# Power-MCU-Breakout.net
KiCad netlist of a schematic drawn in Altium Designer
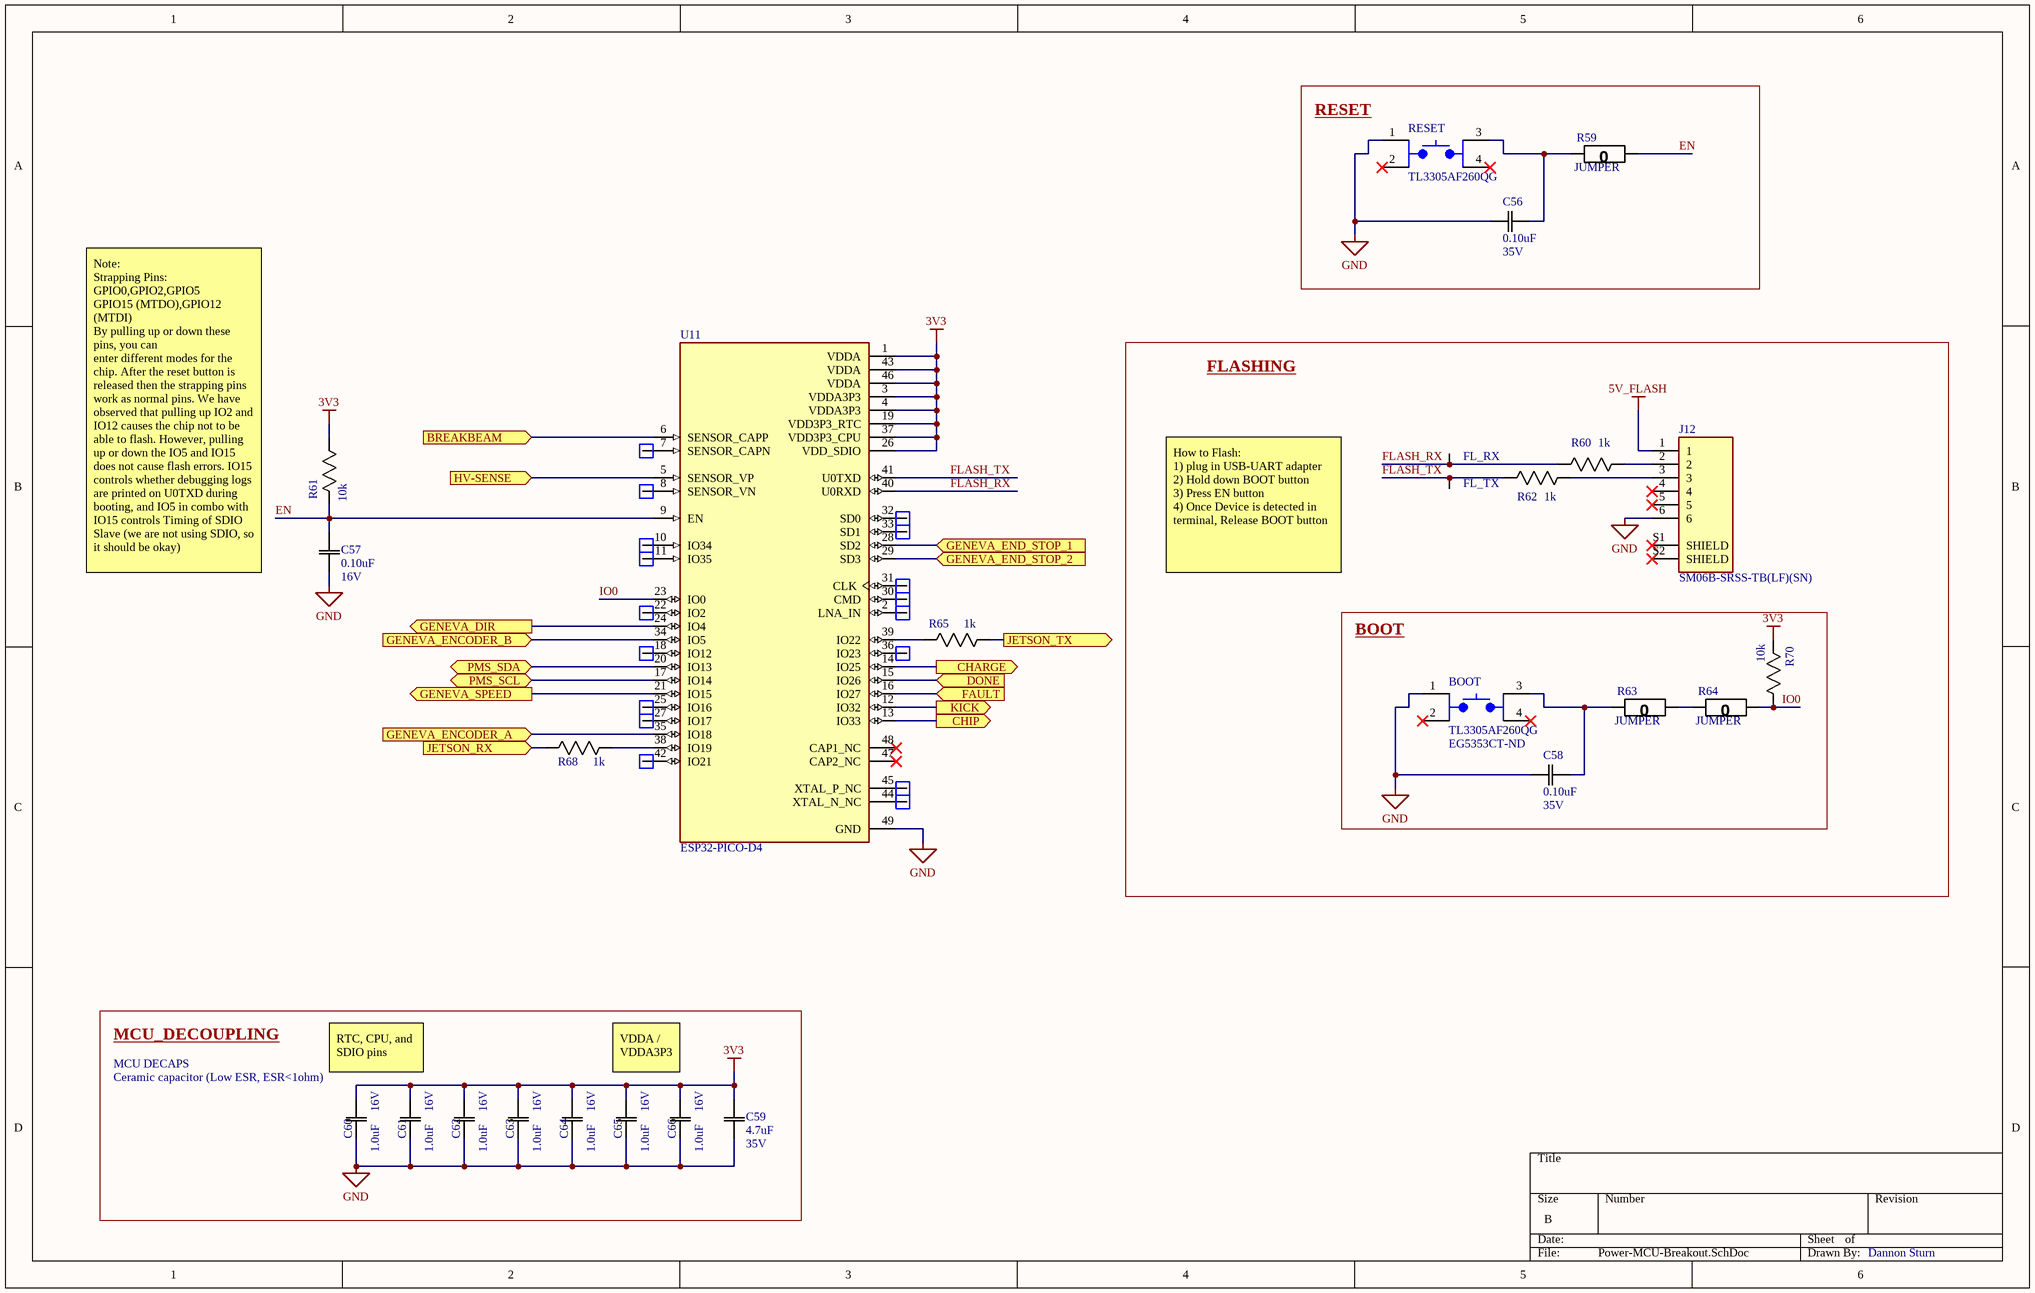
[diagram p0: Power-MCU-Breakout.SchDoc]

(export (version "E")
  (design (tool "Eeschema 10.0.6"))
  (components
    (comp (ref "2")
      (value "Breakout Pin 0603")
      (footprint "BreakoutPin 0603")
      (libsource (lib "AltiumLibraries") (part "Breakout Pin 0603"))
    )
    (comp (ref "7")
      (value "Breakout Pin 0603")
      (footprint "BreakoutPin 0603")
      (libsource (lib "AltiumLibraries") (part "Breakout Pin 0603"))
    )
    (comp (ref "8")
      (value "Breakout Pin 0603")
      (footprint "BreakoutPin 0603")
      (libsource (lib "AltiumLibraries") (part "Breakout Pin 0603"))
    )
    (comp (ref "10")
      (value "Breakout Pin 0603")
      (footprint "BreakoutPin 0603")
      (libsource (lib "AltiumLibraries") (part "Breakout Pin 0603"))
    )
    (comp (ref "11")
      (value "Breakout Pin 0603")
      (footprint "BreakoutPin 0603")
      (libsource (lib "AltiumLibraries") (part "Breakout Pin 0603"))
    )
    (comp (ref "18")
      (value "Breakout Pin 0603")
      (footprint "BreakoutPin 0603")
      (libsource (lib "AltiumLibraries") (part "Breakout Pin 0603"))
    )
    (comp (ref "22")
      (value "Breakout Pin 0603")
      (footprint "BreakoutPin 0603")
      (libsource (lib "AltiumLibraries") (part "Breakout Pin 0603"))
    )
    (comp (ref "25")
      (value "Breakout Pin 0603")
      (footprint "BreakoutPin 0603")
      (libsource (lib "AltiumLibraries") (part "Breakout Pin 0603"))
    )
    (comp (ref "27")
      (value "Breakout Pin 0603")
      (footprint "BreakoutPin 0603")
      (libsource (lib "AltiumLibraries") (part "Breakout Pin 0603"))
    )
    (comp (ref "30")
      (value "Breakout Pin 0603")
      (footprint "BreakoutPin 0603")
      (libsource (lib "AltiumLibraries") (part "Breakout Pin 0603"))
    )
    (comp (ref "31")
      (value "Breakout Pin 0603")
      (footprint "BreakoutPin 0603")
      (libsource (lib "AltiumLibraries") (part "Breakout Pin 0603"))
    )
    (comp (ref "32")
      (value "Breakout Pin 0603")
      (footprint "BreakoutPin 0603")
      (libsource (lib "AltiumLibraries") (part "Breakout Pin 0603"))
    )
    (comp (ref "33")
      (value "Breakout Pin 0603")
      (footprint "BreakoutPin 0603")
      (libsource (lib "AltiumLibraries") (part "Breakout Pin 0603"))
    )
    (comp (ref "36")
      (value "Breakout Pin 0603")
      (footprint "BreakoutPin 0603")
      (libsource (lib "AltiumLibraries") (part "Breakout Pin 0603"))
    )
    (comp (ref "42")
      (value "Breakout Pin 0603")
      (footprint "BreakoutPin 0603")
      (libsource (lib "AltiumLibraries") (part "Breakout Pin 0603"))
    )
    (comp (ref "44")
      (value "Breakout Pin 0603")
      (footprint "BreakoutPin 0603")
      (libsource (lib "AltiumLibraries") (part "Breakout Pin 0603"))
    )
    (comp (ref "45")
      (value "Breakout Pin 0603")
      (footprint "BreakoutPin 0603")
      (libsource (lib "AltiumLibraries") (part "Breakout Pin 0603"))
    )
    (comp (ref "BOOT")
      (value "TL3305AF260QG")
      (footprint "SW_TL3305AF260QG")
      (description "Tactile Switch SPST-NO Top Actuated Surface Mount")
      (fields (field (name "MF") "E-Switch") (field (name "SUPPLIER PART NUMBER 1") "EG5353CT-ND"))
      (libsource (lib "AltiumLibraries") (part "SW PUSH TACT NO SMD"))
    )
    (comp (ref "C56")
      (value "0.10uF")
      (footprint "0603")
      (description "CAP CER 0.10UF 35V X7R 0603/0805")
      (fields (field (name "TOLERANCE") "10%") (field (name "RATING") "35V"))
      (libsource (lib "AltiumLibraries") (part "CAP 0.10uF 35V"))
    )
    (comp (ref "C57")
      (value "0.10uF")
      (footprint "0603")
      (description "CAP CER 0.10UF 16V X5R 0603/0805")
      (fields (field (name "TOLERANCE") "10%") (field (name "RATING") "16V"))
      (libsource (lib "AltiumLibraries") (part "CAP 0.10uF 16V"))
    )
    (comp (ref "C58")
      (value "0.10uF")
      (footprint "0603")
      (description "CAP CER 0.10UF 35V X7R 0603/0805")
      (fields (field (name "TOLERANCE") "10%") (field (name "RATING") "35V"))
      (libsource (lib "AltiumLibraries") (part "CAP 0.10uF 35V"))
    )
    (comp (ref "C59")
      (value "4.7uF")
      (footprint "0603")
      (description "CAP CER 4.7UF 35V X7R 0603/0805")
      (fields (field (name "TOLERANCE") "10%") (field (name "RATING") "35V"))
      (libsource (lib "AltiumLibraries") (part "CAP 4.7uF 35V"))
    )
    (comp (ref "C60")
      (value "1.0uF")
      (footprint "0603")
      (description "CAP CER 1.0UF 16V X5R 0603/0805")
      (fields (field (name "TOLERANCE") "10%") (field (name "RATING") "16V"))
      (libsource (lib "AltiumLibraries") (part "CAP 1.0uF 16V"))
    )
    (comp (ref "C61")
      (value "1.0uF")
      (footprint "0603")
      (description "CAP CER 1.0UF 16V X5R 0603/0805")
      (fields (field (name "TOLERANCE") "10%") (field (name "RATING") "16V"))
      (libsource (lib "AltiumLibraries") (part "CAP 1.0uF 16V"))
    )
    (comp (ref "C62")
      (value "1.0uF")
      (footprint "0603")
      (description "CAP CER 1.0UF 16V X5R 0603/0805")
      (fields (field (name "TOLERANCE") "10%") (field (name "RATING") "16V"))
      (libsource (lib "AltiumLibraries") (part "CAP 1.0uF 16V"))
    )
    (comp (ref "C63")
      (value "1.0uF")
      (footprint "0603")
      (description "CAP CER 1.0UF 16V X5R 0603/0805")
      (fields (field (name "TOLERANCE") "10%") (field (name "RATING") "16V"))
      (libsource (lib "AltiumLibraries") (part "CAP 1.0uF 16V"))
    )
    (comp (ref "C64")
      (value "1.0uF")
      (footprint "0603")
      (description "CAP CER 1.0UF 16V X5R 0603/0805")
      (fields (field (name "TOLERANCE") "10%") (field (name "RATING") "16V"))
      (libsource (lib "AltiumLibraries") (part "CAP 1.0uF 16V"))
    )
    (comp (ref "C65")
      (value "1.0uF")
      (footprint "0603")
      (description "CAP CER 1.0UF 16V X5R 0603/0805")
      (fields (field (name "TOLERANCE") "10%") (field (name "RATING") "16V"))
      (libsource (lib "AltiumLibraries") (part "CAP 1.0uF 16V"))
    )
    (comp (ref "C66")
      (value "1.0uF")
      (footprint "0603")
      (description "CAP CER 1.0UF 16V X5R 0603/0805")
      (fields (field (name "TOLERANCE") "10%") (field (name "RATING") "16V"))
      (libsource (lib "AltiumLibraries") (part "CAP 1.0uF 16V"))
    )
    (comp (ref "FL_RX")
      (value "Test Point (Via)")
      (footprint "TP")
      (libsource (lib "AltiumLibraries") (part "Test Point (Via)"))
    )
    (comp (ref "FL_TX")
      (value "Test Point (Via)")
      (footprint "TP")
      (libsource (lib "AltiumLibraries") (part "Test Point (Via)"))
    )
    (comp (ref "J12")
      (value "SM06B-SRSS-TB(LF)(SN)")
      (footprint "JST_SM06B-SRSS-TB(LF)(SN)")
      (description "Connector Header Surface Mount, Right Angle 6 position 0.039 _1.00mm_")
      (fields
        (field (name "MP") "SM06B-SRSS-TB_LF__SN_")
        (field (name "DIGI-KEY_PART_NUMBER") "455-1806-1-ND")
      )
      (libsource (lib "AltiumLibraries") (part "CN 6POS JST SR SMT"))
    )
    (comp (ref "R59")
      (value "JUMPER")
      (footprint "0603")
      (description "RES SMD 0 OHM JUMPER GENERIC 0805/0603")
      (libsource (lib "AltiumLibraries") (part "RES 0 JUMPER"))
    )
    (comp (ref "R60")
      (value "1k")
      (footprint "0603")
      (description "RES SMD 1K OHM 1% 1/8W 0603/0805")
      (fields (field (name "TOLERANCE") "1%"))
      (libsource (lib "AltiumLibraries") (part "RES 1k 1/8W - 1%"))
    )
    (comp (ref "R61")
      (value "10k")
      (footprint "0603")
      (description "RES SMD 10K OHM 5% 1/8W 0805/0603")
      (fields (field (name "TOLERANCE") "5%"))
      (libsource (lib "") (part "RES 10k 1/8W - 5%_1"))
    )
    (comp (ref "R62")
      (value "1k")
      (footprint "0603")
      (description "RES SMD 1K OHM 1% 1/8W 0603/0805")
      (fields (field (name "TOLERANCE") "1%"))
      (libsource (lib "AltiumLibraries") (part "RES 1k 1/8W - 1%"))
    )
    (comp (ref "R63")
      (value "JUMPER")
      (footprint "0603")
      (description "RES SMD 0 OHM JUMPER GENERIC 0805/0603")
      (libsource (lib "AltiumLibraries") (part "RES 0 JUMPER"))
    )
    (comp (ref "R64")
      (value "JUMPER")
      (footprint "0603")
      (description "RES SMD 0 OHM JUMPER GENERIC 0805/0603")
      (libsource (lib "AltiumLibraries") (part "RES 0 JUMPER"))
    )
    (comp (ref "R65")
      (value "1k")
      (footprint "0603")
      (description "RES SMD 1K OHM 1% 1/8W 0603/0805")
      (fields (field (name "TOLERANCE") "1%"))
      (libsource (lib "AltiumLibraries") (part "RES 1k 1/8W - 1%"))
    )
    (comp (ref "R68")
      (value "1k")
      (footprint "0603")
      (description "RES SMD 1K OHM 1% 1/8W 0603/0805")
      (fields (field (name "TOLERANCE") "1%"))
      (libsource (lib "AltiumLibraries") (part "RES 1k 1/8W - 1%"))
    )
    (comp (ref "R70")
      (value "10k")
      (footprint "0603")
      (description "RES SMD 10K OHM 5% 1/8W 0805/0603")
      (fields (field (name "TOLERANCE") "5%"))
      (libsource (lib "AltiumLibraries") (part "RES 10k 1/8W - 5%"))
    )
    (comp (ref "RESET")
      (value "TL3305AF260QG")
      (footprint "SW_TL3305AF260QG")
      (description "Tactile Switch SPST-NO Top Actuated Surface Mount")
      (fields (field (name "MF") "E-Switch"))
      (libsource (lib "AltiumLibraries") (part "SW PUSH TACT NO SMD"))
    )
    (comp (ref "U11")
      (value "ESP32-PICO-D4")
      (footprint "PQFN50P700X700X104-49N - BigPads")
      (fields (field (name "MF") "Espressif Systems"))
      (libsource (lib "AltiumLibraries") (part "ESP32-PICO-D4"))
    )
  )
  (nets
    (net (code "1") (name "/BREAKBEAM") (class "Default")
      (node (ref "U11") (pin "6") (pinfunction "SENSOR_CAPP_6") (pintype "input"))
    )
    (net (code "2") (name "/CHARGE") (class "Default")
      (node (ref "U11") (pin "14") (pinfunction "IO25_14") (pintype "bidirectional"))
    )
    (net (code "3") (name "/CHIP") (class "Default")
      (node (ref "U11") (pin "13") (pinfunction "IO33_13") (pintype "bidirectional"))
    )
    (net (code "4") (name "/DONE") (class "Default")
      (node (ref "U11") (pin "15") (pinfunction "IO26_15") (pintype "bidirectional"))
    )
    (net (code "5") (name "/EN") (class "Default")
      (node (ref "C57") (pin "2") (pinfunction "C2_2") (pintype "passive"))
      (node (ref "R59") (pin "1") (pinfunction "R1_1") (pintype "passive"))
      (node (ref "R61") (pin "2") (pinfunction "R2_2") (pintype "passive"))
      (node (ref "U11") (pin "9") (pinfunction "EN_9") (pintype "input"))
    )
    (net (code "6") (name "/FAULT") (class "Default")
      (node (ref "U11") (pin "16") (pinfunction "IO27_16") (pintype "bidirectional"))
    )
    (net (code "7") (name "/FLASH_RX") (class "Default")
      (node (ref "FL_RX") (pin "1") (pinfunction "1_1") (pintype "passive"))
      (node (ref "R60") (pin "2") (pinfunction "R2_2") (pintype "passive"))
      (node (ref "U11") (pin "40") (pinfunction "U0RXD_40") (pintype "bidirectional"))
    )
    (net (code "8") (name "/FLASH_TX") (class "Default")
      (node (ref "FL_TX") (pin "1") (pinfunction "1_1") (pintype "passive"))
      (node (ref "R62") (pin "2") (pinfunction "R2_2") (pintype "passive"))
      (node (ref "U11") (pin "41") (pinfunction "U0TXD_41") (pintype "bidirectional"))
    )
    (net (code "9") (name "/GENEVA_DIR") (class "Default")
      (node (ref "U11") (pin "24") (pinfunction "IO4_24") (pintype "bidirectional"))
    )
    (net (code "10") (name "/GENEVA_ENCODER_A") (class "Default")
      (node (ref "U11") (pin "35") (pinfunction "IO18_35") (pintype "bidirectional"))
    )
    (net (code "11") (name "/GENEVA_ENCODER_B") (class "Default")
      (node (ref "U11") (pin "34") (pinfunction "IO5_34") (pintype "bidirectional"))
    )
    (net (code "12") (name "/GENEVA_END_STOP_1") (class "Default")
      (node (ref "U11") (pin "28") (pinfunction "SD2_28") (pintype "bidirectional"))
    )
    (net (code "13") (name "/GENEVA_END_STOP_2") (class "Default")
      (node (ref "U11") (pin "29") (pinfunction "SD3_29") (pintype "bidirectional"))
    )
    (net (code "14") (name "/GENEVA_SPEED") (class "Default")
      (node (ref "U11") (pin "21") (pinfunction "IO15_21") (pintype "bidirectional"))
    )
    (net (code "15") (name "/HV-SENSE") (class "Default")
      (node (ref "U11") (pin "5") (pinfunction "SENSOR_VP_5") (pintype "input"))
    )
    (net (code "16") (name "/IO0") (class "Default")
      (node (ref "R64") (pin "1") (pinfunction "R1_1") (pintype "passive"))
      (node (ref "R70") (pin "1") (pinfunction "R1_1") (pintype "passive"))
      (node (ref "U11") (pin "23") (pinfunction "IO0_23") (pintype "bidirectional"))
    )
    (net (code "17") (name "/JETSON_RX") (class "Default")
      (node (ref "R68") (pin "2") (pinfunction "R2_2") (pintype "passive"))
    )
    (net (code "18") (name "/JETSON_TX") (class "Default")
      (node (ref "R65") (pin "1") (pinfunction "R1_1") (pintype "passive"))
    )
    (net (code "19") (name "/KICK") (class "Default")
      (node (ref "U11") (pin "12") (pinfunction "IO32_12") (pintype "bidirectional"))
    )
    (net (code "20") (name "/PMS_SCL") (class "Default")
      (node (ref "U11") (pin "17") (pinfunction "IO14_17") (pintype "bidirectional"))
    )
    (net (code "21") (name "/PMS_SDA") (class "Default")
      (node (ref "U11") (pin "20") (pinfunction "IO13_20") (pintype "bidirectional"))
    )
    (net (code "22") (name "3V3") (class "Default")
      (node (ref "C59") (pin "2") (pinfunction "C2_2") (pintype "passive"))
      (node (ref "C60") (pin "2") (pinfunction "C2_2") (pintype "passive"))
      (node (ref "C61") (pin "2") (pinfunction "C2_2") (pintype "passive"))
      (node (ref "C62") (pin "2") (pinfunction "C2_2") (pintype "passive"))
      (node (ref "C63") (pin "2") (pinfunction "C2_2") (pintype "passive"))
      (node (ref "C64") (pin "2") (pinfunction "C2_2") (pintype "passive"))
      (node (ref "C65") (pin "2") (pinfunction "C2_2") (pintype "passive"))
      (node (ref "C66") (pin "2") (pinfunction "C2_2") (pintype "passive"))
      (node (ref "R61") (pin "1") (pinfunction "R1_1") (pintype "passive"))
      (node (ref "R70") (pin "2") (pinfunction "R2_2") (pintype "passive"))
      (node (ref "U11") (pin "1") (pinfunction "VDDA_1") (pintype "power_in"))
      (node (ref "U11") (pin "19") (pinfunction "VDD3P3_RTC_19") (pintype "power_in"))
      (node (ref "U11") (pin "26") (pinfunction "VDD_SDIO_26") (pintype "power_in"))
      (node (ref "U11") (pin "3") (pinfunction "VDDA3P3_3") (pintype "power_in"))
      (node (ref "U11") (pin "37") (pinfunction "VDD3P3_CPU_37") (pintype "power_in"))
      (node (ref "U11") (pin "4") (pinfunction "VDDA3P3_4") (pintype "power_in"))
      (node (ref "U11") (pin "43") (pinfunction "VDDA_43") (pintype "power_in"))
      (node (ref "U11") (pin "46") (pinfunction "VDDA_46") (pintype "power_in"))
    )
    (net (code "23") (name "5V_FLASH") (class "Default")
      (node (ref "J12") (pin "1") (pinfunction "1_1") (pintype "passive"))
    )
    (net (code "24") (name "GND") (class "Default")
      (node (ref "BOOT") (pin "1") (pinfunction "1_1") (pintype "passive"))
      (node (ref "C56") (pin "1") (pinfunction "C1_1") (pintype "passive"))
      (node (ref "C57") (pin "1") (pinfunction "C1_1") (pintype "passive"))
      (node (ref "C58") (pin "1") (pinfunction "C1_1") (pintype "passive"))
      (node (ref "C59") (pin "1") (pinfunction "C1_1") (pintype "passive"))
      (node (ref "C60") (pin "1") (pinfunction "C1_1") (pintype "passive"))
      (node (ref "C61") (pin "1") (pinfunction "C1_1") (pintype "passive"))
      (node (ref "C62") (pin "1") (pinfunction "C1_1") (pintype "passive"))
      (node (ref "C63") (pin "1") (pinfunction "C1_1") (pintype "passive"))
      (node (ref "C64") (pin "1") (pinfunction "C1_1") (pintype "passive"))
      (node (ref "C65") (pin "1") (pinfunction "C1_1") (pintype "passive"))
      (node (ref "C66") (pin "1") (pinfunction "C1_1") (pintype "passive"))
      (node (ref "J12") (pin "6") (pinfunction "6_6") (pintype "passive"))
      (node (ref "RESET") (pin "1") (pinfunction "1_1") (pintype "passive"))
      (node (ref "U11") (pin "49") (pinfunction "GND_49") (pintype "power_in"))
    )
    (net (code "25") (name "Net-(2-BRKOUT)") (class "Default")
      (node (ref "2") (pin "1") (pinfunction "BRKOUT_1") (pintype "passive"))
      (node (ref "U11") (pin "2") (pinfunction "LNA_IN_2") (pintype "bidirectional"))
    )
    (net (code "26") (name "Net-(7-BRKOUT)") (class "Default")
      (node (ref "7") (pin "1") (pinfunction "BRKOUT_1") (pintype "passive"))
      (node (ref "U11") (pin "7") (pinfunction "SENSOR_CAPN_7") (pintype "input"))
    )
    (net (code "27") (name "Net-(8-BRKOUT)") (class "Default")
      (node (ref "8") (pin "1") (pinfunction "BRKOUT_1") (pintype "passive"))
      (node (ref "U11") (pin "8") (pinfunction "SENSOR_VN_8") (pintype "input"))
    )
    (net (code "28") (name "Net-(10-BRKOUT)") (class "Default")
      (node (ref "10") (pin "1") (pinfunction "BRKOUT_1") (pintype "passive"))
      (node (ref "U11") (pin "10") (pinfunction "IO34_10") (pintype "input"))
    )
    (net (code "29") (name "Net-(11-BRKOUT)") (class "Default")
      (node (ref "11") (pin "1") (pinfunction "BRKOUT_1") (pintype "passive"))
      (node (ref "U11") (pin "11") (pinfunction "IO35_11") (pintype "input"))
    )
    (net (code "30") (name "Net-(18-BRKOUT)") (class "Default")
      (node (ref "18") (pin "1") (pinfunction "BRKOUT_1") (pintype "passive"))
      (node (ref "U11") (pin "18") (pinfunction "IO12_18") (pintype "bidirectional"))
    )
    (net (code "31") (name "Net-(22-BRKOUT)") (class "Default")
      (node (ref "22") (pin "1") (pinfunction "BRKOUT_1") (pintype "passive"))
      (node (ref "U11") (pin "22") (pinfunction "IO2_22") (pintype "bidirectional"))
    )
    (net (code "32") (name "Net-(25-BRKOUT)") (class "Default")
      (node (ref "25") (pin "1") (pinfunction "BRKOUT_1") (pintype "passive"))
      (node (ref "U11") (pin "25") (pinfunction "IO16_25") (pintype "bidirectional"))
    )
    (net (code "33") (name "Net-(27-BRKOUT)") (class "Default")
      (node (ref "27") (pin "1") (pinfunction "BRKOUT_1") (pintype "passive"))
      (node (ref "U11") (pin "27") (pinfunction "IO17_27") (pintype "bidirectional"))
    )
    (net (code "34") (name "Net-(30-BRKOUT)") (class "Default")
      (node (ref "30") (pin "1") (pinfunction "BRKOUT_1") (pintype "passive"))
      (node (ref "U11") (pin "30") (pinfunction "CMD_30") (pintype "bidirectional"))
    )
    (net (code "35") (name "Net-(31-BRKOUT)") (class "Default")
      (node (ref "31") (pin "1") (pinfunction "BRKOUT_1") (pintype "passive"))
      (node (ref "U11") (pin "31") (pinfunction "CLK_31") (pintype "bidirectional"))
    )
    (net (code "36") (name "Net-(32-BRKOUT)") (class "Default")
      (node (ref "32") (pin "1") (pinfunction "BRKOUT_1") (pintype "passive"))
      (node (ref "U11") (pin "32") (pinfunction "SD0_32") (pintype "bidirectional"))
    )
    (net (code "37") (name "Net-(33-BRKOUT)") (class "Default")
      (node (ref "33") (pin "1") (pinfunction "BRKOUT_1") (pintype "passive"))
      (node (ref "U11") (pin "33") (pinfunction "SD1_33") (pintype "bidirectional"))
    )
    (net (code "38") (name "Net-(36-BRKOUT)") (class "Default")
      (node (ref "36") (pin "1") (pinfunction "BRKOUT_1") (pintype "passive"))
      (node (ref "U11") (pin "36") (pinfunction "IO23_36") (pintype "bidirectional"))
    )
    (net (code "39") (name "Net-(42-BRKOUT)") (class "Default")
      (node (ref "42") (pin "1") (pinfunction "BRKOUT_1") (pintype "passive"))
      (node (ref "U11") (pin "42") (pinfunction "IO21_42") (pintype "bidirectional"))
    )
    (net (code "40") (name "Net-(44-BRKOUT)") (class "Default")
      (node (ref "44") (pin "1") (pinfunction "BRKOUT_1") (pintype "passive"))
      (node (ref "U11") (pin "44") (pinfunction "XTAL_N_NC_44") (pintype "passive"))
    )
    (net (code "41") (name "Net-(45-BRKOUT)") (class "Default")
      (node (ref "45") (pin "1") (pinfunction "BRKOUT_1") (pintype "passive"))
      (node (ref "U11") (pin "45") (pinfunction "XTAL_P_NC_45") (pintype "passive"))
    )
    (net (code "42") (name "Net-(C56-C2)") (class "Default")
      (node (ref "C56") (pin "2") (pinfunction "C2_2") (pintype "passive"))
      (node (ref "R59") (pin "2") (pinfunction "R2_2") (pintype "passive"))
      (node (ref "RESET") (pin "3") (pinfunction "3_3") (pintype "passive"))
    )
    (net (code "43") (name "Net-(C58-C2)") (class "Default")
      (node (ref "BOOT") (pin "3") (pinfunction "3_3") (pintype "passive"))
      (node (ref "C58") (pin "2") (pinfunction "C2_2") (pintype "passive"))
      (node (ref "R63") (pin "2") (pinfunction "R2_2") (pintype "passive"))
    )
    (net (code "44") (name "Net-(R60-R1)") (class "Default")
      (node (ref "J12") (pin "2") (pinfunction "2_2") (pintype "passive"))
      (node (ref "R60") (pin "1") (pinfunction "R1_1") (pintype "passive"))
    )
    (net (code "45") (name "Net-(R62-R1)") (class "Default")
      (node (ref "J12") (pin "3") (pinfunction "3_3") (pintype "passive"))
      (node (ref "R62") (pin "1") (pinfunction "R1_1") (pintype "passive"))
    )
    (net (code "46") (name "Net-(R63-R1)") (class "Default")
      (node (ref "R63") (pin "1") (pinfunction "R1_1") (pintype "passive"))
      (node (ref "R64") (pin "2") (pinfunction "R2_2") (pintype "passive"))
    )
    (net (code "47") (name "Net-(R65-R2)") (class "Default")
      (node (ref "R65") (pin "2") (pinfunction "R2_2") (pintype "passive"))
      (node (ref "U11") (pin "39") (pinfunction "IO22_39") (pintype "bidirectional"))
    )
    (net (code "48") (name "Net-(R68-R1)") (class "Default")
      (node (ref "R68") (pin "1") (pinfunction "R1_1") (pintype "passive"))
      (node (ref "U11") (pin "38") (pinfunction "IO19_38") (pintype "bidirectional"))
    )
    (net (code "49") (name "unconnected-(BOOT-Pad2)") (class "Default")
      (node (ref "BOOT") (pin "2") (pinfunction "2_2") (pintype "passive+no_connect"))
    )
    (net (code "50") (name "unconnected-(BOOT-Pad4)") (class "Default")
      (node (ref "BOOT") (pin "4") (pinfunction "4_4") (pintype "passive+no_connect"))
    )
    (net (code "51") (name "unconnected-(J12-Pad4)") (class "Default")
      (node (ref "J12") (pin "4") (pinfunction "4_4") (pintype "passive+no_connect"))
    )
    (net (code "52") (name "unconnected-(J12-Pad5)") (class "Default")
      (node (ref "J12") (pin "5") (pinfunction "5_5") (pintype "passive+no_connect"))
    )
    (net (code "53") (name "unconnected-(J12-SHIELD-PadS1)") (class "Default")
      (node (ref "J12") (pin "S1") (pinfunction "SHIELD_S1") (pintype "passive+no_connect"))
    )
    (net (code "54") (name "unconnected-(J12-SHIELD-PadS2)") (class "Default")
      (node (ref "J12") (pin "S2") (pinfunction "SHIELD_S2") (pintype "passive+no_connect"))
    )
    (net (code "55") (name "unconnected-(RESET-Pad2)") (class "Default")
      (node (ref "RESET") (pin "2") (pinfunction "2_2") (pintype "passive+no_connect"))
    )
    (net (code "56") (name "unconnected-(RESET-Pad4)") (class "Default")
      (node (ref "RESET") (pin "4") (pinfunction "4_4") (pintype "passive+no_connect"))
    )
    (net (code "57") (name "unconnected-(U11-CAP1_NC-Pad48)") (class "Default")
      (node (ref "U11") (pin "48") (pinfunction "CAP1_NC_48") (pintype "passive+no_connect"))
    )
    (net (code "58") (name "unconnected-(U11-CAP2_NC-Pad47)") (class "Default")
      (node (ref "U11") (pin "47") (pinfunction "CAP2_NC_47") (pintype "passive+no_connect"))
    )
  )
)
